# charger_pcb.net
KiCad netlist of a schematic drawn in EAGLE
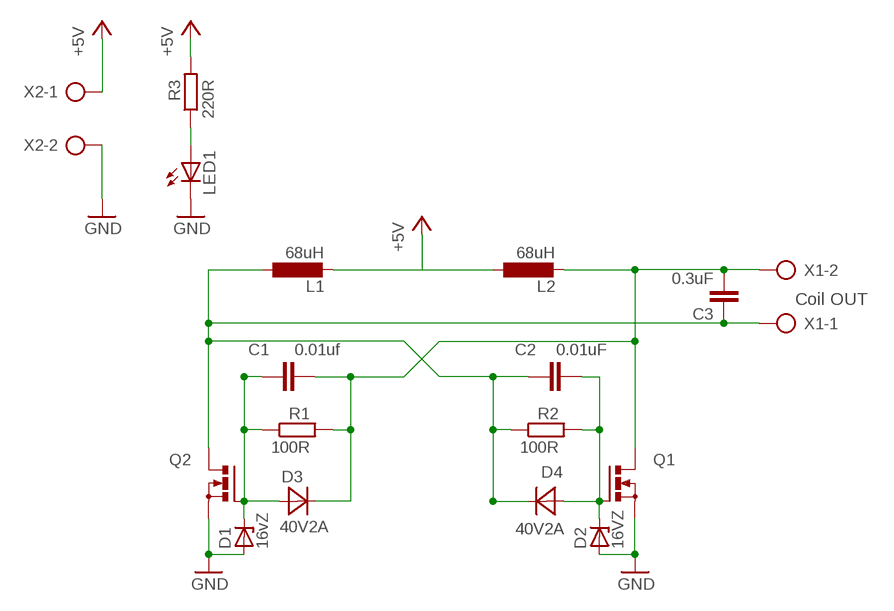
[diagram p0: schematic, sheet 1]

(export (version "E")
  (design (tool "Eeschema 10.0.6"))
  (components
    (comp (ref "C1")
      (value "0.01uf")
      (footprint "eagle-import:C0805")
      (libsource (lib "eagle-import") (part "C-EUC0805"))
    )
    (comp (ref "C2")
      (value "0.01uF")
      (footprint "eagle-import:C0805")
      (libsource (lib "eagle-import") (part "C-EUC0805"))
    )
    (comp (ref "C3")
      (value "0.3uF")
      (footprint "eagle-import:C0805")
      (libsource (lib "eagle-import") (part "C-EUC0805"))
    )
    (comp (ref "D1")
      (value "16vZ")
      (footprint "eagle-import:SOD80C")
      (libsource (lib "eagle-import") (part "ZENER-DIODESOD80C"))
    )
    (comp (ref "D2")
      (value "16VZ")
      (footprint "eagle-import:SOD80C")
      (libsource (lib "eagle-import") (part "ZENER-DIODESOD80C"))
    )
    (comp (ref "D3")
      (value "40V2A")
      (footprint "eagle-import:SMA")
      (libsource (lib "eagle-import") (part "MBRA340T3"))
    )
    (comp (ref "D4")
      (value "40V2A")
      (footprint "eagle-import:SMA")
      (libsource (lib "eagle-import") (part "MBRA340T3"))
    )
    (comp (ref "L1")
      (value "68uH")
      (footprint "eagle-import:L5650M")
      (libsource (lib "eagle-import") (part "L-EUL5650M"))
    )
    (comp (ref "L2")
      (value "68uH")
      (footprint "eagle-import:L5650M")
      (libsource (lib "eagle-import") (part "L-EUL5650M"))
    )
    (comp (ref "LED1")
      (value "LEDCHIP-LED0805")
      (footprint "eagle-import:CHIP-LED0805")
      (libsource (lib "eagle-import") (part "LEDCHIP-LED0805"))
    )
    (comp (ref "Q1")
      (value "N-MOSFET-SO8S")
      (footprint "eagle-import:SO-08")
      (libsource (lib "eagle-import") (part "N-MOSFET-SO8S"))
    )
    (comp (ref "Q2")
      (value "N-MOSFET-SO8S")
      (footprint "eagle-import:SO-08")
      (libsource (lib "eagle-import") (part "N-MOSFET-SO8S"))
    )
    (comp (ref "R1")
      (value "100R")
      (footprint "eagle-import:R0805")
      (libsource (lib "eagle-import") (part "R-EU_R0805"))
    )
    (comp (ref "R2")
      (value "100R")
      (footprint "eagle-import:R0805")
      (libsource (lib "eagle-import") (part "R-EU_R0805"))
    )
    (comp (ref "R3")
      (value "220R")
      (footprint "eagle-import:R0805")
      (libsource (lib "eagle-import") (part "R-EU_R0805"))
    )
    (comp (ref "X1")
      (value "AK500/2")
      (footprint "eagle-import:AK500_2")
      (libsource (lib "eagle-import") (part "AK500/2"))
    )
    (comp (ref "X2")
      (value "AK500/2")
      (footprint "eagle-import:AK500_2")
      (libsource (lib "eagle-import") (part "AK500/2"))
    )
  )
  (nets
    (net (code "1") (name "+5V") (class "Default")
      (node (ref "L1") (pin "2") (pinfunction "2_2") (pintype "passive"))
      (node (ref "L2") (pin "1") (pinfunction "1_1") (pintype "passive"))
      (node (ref "R3") (pin "2") (pinfunction "2_2") (pintype "passive"))
      (node (ref "X2") (pin "1") (pinfunction "KL_1") (pintype "passive"))
    )
    (net (code "2") (name "GND") (class "Default")
      (node (ref "D1") (pin "A") (pinfunction "A_A") (pintype "passive"))
      (node (ref "D2") (pin "A") (pinfunction "A_A") (pintype "passive"))
      (node (ref "LED1") (pin "C") (pinfunction "C_C") (pintype "passive"))
      (node (ref "Q1") (pin "1") (pinfunction "S_1") (pintype "passive"))
      (node (ref "Q1") (pin "2") (pinfunction "S_2") (pintype "passive"))
      (node (ref "Q1") (pin "3") (pinfunction "S_3") (pintype "passive"))
      (node (ref "Q2") (pin "1") (pinfunction "S_1") (pintype "passive"))
      (node (ref "Q2") (pin "2") (pinfunction "S_2") (pintype "passive"))
      (node (ref "Q2") (pin "3") (pinfunction "S_3") (pintype "passive"))
      (node (ref "X2") (pin "2") (pinfunction "KL_2") (pintype "passive"))
    )
    (net (code "3") (name "Net-(LED1-PadA)") (class "Default")
      (node (ref "LED1") (pin "A") (pinfunction "A_A") (pintype "passive"))
      (node (ref "R3") (pin "1") (pinfunction "1_1") (pintype "passive"))
    )
    (net (code "4") (name "Net-(Q1-G)") (class "Default")
      (node (ref "C2") (pin "2") (pinfunction "2_2") (pintype "passive"))
      (node (ref "D2") (pin "C") (pinfunction "C_C") (pintype "passive"))
      (node (ref "D4") (pin "A") (pinfunction "A_A") (pintype "passive"))
      (node (ref "Q1") (pin "4") (pinfunction "G_4") (pintype "passive"))
      (node (ref "R2") (pin "2") (pinfunction "2_2") (pintype "passive"))
    )
    (net (code "5") (name "Net-(Q2-G)") (class "Default")
      (node (ref "C1") (pin "1") (pinfunction "1_1") (pintype "passive"))
      (node (ref "D1") (pin "C") (pinfunction "C_C") (pintype "passive"))
      (node (ref "D3") (pin "A") (pinfunction "A_A") (pintype "passive"))
      (node (ref "Q2") (pin "4") (pinfunction "G_4") (pintype "passive"))
      (node (ref "R1") (pin "1") (pinfunction "1_1") (pintype "passive"))
    )
    (net (code "6") (name "Net-(X1A-KL)") (class "Default")
      (node (ref "C2") (pin "1") (pinfunction "1_1") (pintype "passive"))
      (node (ref "C3") (pin "1") (pinfunction "1_1") (pintype "passive"))
      (node (ref "D4") (pin "C") (pinfunction "C_C") (pintype "passive"))
      (node (ref "L1") (pin "1") (pinfunction "1_1") (pintype "passive"))
      (node (ref "Q2") (pin "5") (pinfunction "D_5") (pintype "passive"))
      (node (ref "Q2") (pin "6") (pinfunction "D_6") (pintype "passive"))
      (node (ref "Q2") (pin "7") (pinfunction "D_7") (pintype "passive"))
      (node (ref "Q2") (pin "8") (pinfunction "D_8") (pintype "passive"))
      (node (ref "R2") (pin "1") (pinfunction "1_1") (pintype "passive"))
      (node (ref "X1") (pin "1") (pinfunction "KL_1") (pintype "passive"))
    )
    (net (code "7") (name "Net-(X1B-KL)") (class "Default")
      (node (ref "C1") (pin "2") (pinfunction "2_2") (pintype "passive"))
      (node (ref "C3") (pin "2") (pinfunction "2_2") (pintype "passive"))
      (node (ref "D3") (pin "C") (pinfunction "C_C") (pintype "passive"))
      (node (ref "L2") (pin "2") (pinfunction "2_2") (pintype "passive"))
      (node (ref "Q1") (pin "5") (pinfunction "D_5") (pintype "passive"))
      (node (ref "Q1") (pin "6") (pinfunction "D_6") (pintype "passive"))
      (node (ref "Q1") (pin "7") (pinfunction "D_7") (pintype "passive"))
      (node (ref "Q1") (pin "8") (pinfunction "D_8") (pintype "passive"))
      (node (ref "R1") (pin "2") (pinfunction "2_2") (pintype "passive"))
      (node (ref "X1") (pin "2") (pinfunction "KL_2") (pintype "passive"))
    )
  )
)
